# SCH_HUD_Speedo_EasyEDA.net
KiCad netlist of a schematic drawn in EasyEDA
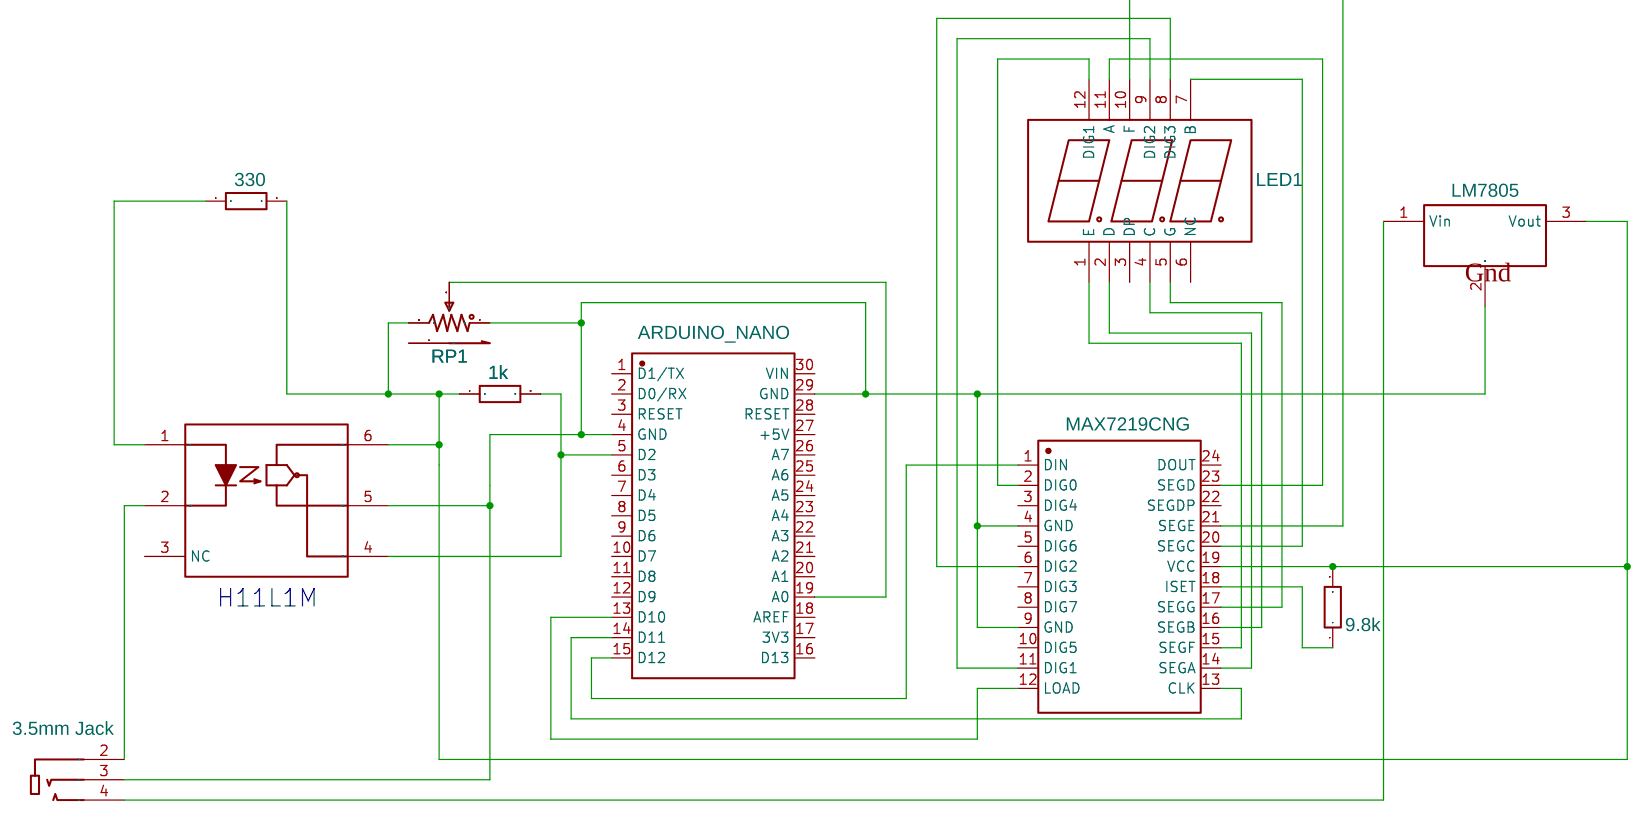
[diagram p0: schematic sheet]

(export (version "E")
  (design (tool "Eeschema 10.0.6"))
  (components
    (comp (ref "ARDUINO_NANO")
      (value "ARDUINO_NANO")
      (fields (field (name "BOM_Supplier Part") "C9900017879"))
      (libsource (lib "") (part "ARDUINO_NANO"))
    )
    (comp (ref "CN1")
      (value "3.5mm Jack")
      (fields (field (name "BOM_Manufacturer Part") "PJ-3136-B") (field (name "BOM_Supplier Part") "C381131"))
      (libsource (lib "") (part "PJ-3136-B"))
    )
    (comp (ref "DA1") (value "LM7805") (libsource (lib "") (part "LM7805")))
    (comp (ref "LED1")
      (value "SLR0523DWC1BD")
      (fields (field (name "BOM_Supplier Part") "C225931"))
      (libsource (lib "") (part "SLR0523DWC1BD"))
    )
    (comp (ref "R1")
      (value "9.8k")
      (fields
        (field (name "BOM_Manufacturer Part") "MFR0W4F1503A50")
        (field (name "BOM_Supplier Part") "C58618")
      )
      (libsource (lib "") (part "MFR0W4F1503A50_1"))
    )
    (comp (ref "R2")
      (value "330")
      (fields
        (field (name "BOM_Manufacturer Part") "MFR0W4F1503A50")
        (field (name "BOM_Supplier Part") "C58618")
      )
      (libsource (lib "") (part "MFR0W4F1503A50"))
    )
    (comp (ref "R3")
      (value "1k")
      (fields
        (field (name "BOM_Manufacturer Part") "MFR0W4F1503A50")
        (field (name "BOM_Supplier Part") "C58618")
      )
      (libsource (lib "") (part "MFR0W4F1503A50"))
    )
    (comp (ref "RP1")
      (value "RK09K1130ACM")
      (fields (field (name "BOM_Supplier Part") "C470290"))
      (libsource (lib "") (part "RK09K1130ACM"))
    )
    (comp (ref "U1")
      (value "MAX7219CNG")
      (fields (field (name "BOM_Manufacturer Part") "max7219cng") (field (name "BOM_Supplier Part") "C29160"))
      (libsource (lib "") (part "max7219cng"))
    )
    (comp (ref "U5")
      (value "H11L1M")
      (fields (field (name "BOM_Supplier Part") "C16587"))
      (libsource (lib "") (part "H11L1M"))
    )
  )
  (nets
    (net (code "1") (name "Net-(ARDUINO_NANO-A0)") (class "Default")
      (node (ref "ARDUINO_NANO") (pin "19") (pinfunction "A0_19") (pintype "unspecified"))
      (node (ref "RP1") (pin "2") (pinfunction "2_2") (pintype "unspecified"))
    )
    (net (code "2") (name "Net-(ARDUINO_NANO-D2)") (class "Default")
      (node (ref "ARDUINO_NANO") (pin "5") (pinfunction "D2_5") (pintype "unspecified"))
      (node (ref "R3") (pin "2") (pinfunction "2_2") (pintype "input"))
      (node (ref "U5") (pin "4") (pinfunction "VO_4") (pintype "unspecified"))
    )
    (net (code "3") (name "Net-(ARDUINO_NANO-D10)") (class "Default")
      (node (ref "ARDUINO_NANO") (pin "13") (pinfunction "D10_13") (pintype "unspecified"))
      (node (ref "U1") (pin "12") (pinfunction "LOAD_12") (pintype "unspecified"))
    )
    (net (code "4") (name "Net-(ARDUINO_NANO-D11)") (class "Default")
      (node (ref "ARDUINO_NANO") (pin "14") (pinfunction "D11_14") (pintype "unspecified"))
      (node (ref "U1") (pin "13") (pinfunction "CLK_13") (pintype "unspecified"))
    )
    (net (code "5") (name "Net-(ARDUINO_NANO-D12)") (class "Default")
      (node (ref "ARDUINO_NANO") (pin "15") (pinfunction "D12_15") (pintype "unspecified"))
      (node (ref "U1") (pin "1") (pinfunction "DIN_1") (pintype "unspecified"))
    )
    (net (code "6") (name "Net-(DA1-GND)") (class "Default")
      (node (ref "ARDUINO_NANO") (pin "29") (pinfunction "GND_29") (pintype "unspecified"))
      (node (ref "ARDUINO_NANO") (pin "4") (pinfunction "GND_4") (pintype "unspecified"))
      (node (ref "CN1") (pin "3") (pinfunction "3_3") (pintype "unspecified"))
      (node (ref "DA1") (pin "2") (pinfunction "GND_2") (pintype "unspecified"))
      (node (ref "RP1") (pin "1") (pinfunction "1_1") (pintype "unspecified"))
      (node (ref "U1") (pin "4") (pinfunction "GND_4") (pintype "unspecified"))
      (node (ref "U1") (pin "9") (pinfunction "GND_9") (pintype "unspecified"))
      (node (ref "U5") (pin "5") (pinfunction "GND_5") (pintype "unspecified"))
    )
    (net (code "7") (name "Net-(DA1-Vin)") (class "Default")
      (node (ref "CN1") (pin "4") (pinfunction "4_4") (pintype "unspecified"))
      (node (ref "DA1") (pin "1") (pinfunction "Vin_1") (pintype "unspecified"))
    )
    (net (code "8") (name "Net-(DA1-Vout)") (class "Default")
      (node (ref "DA1") (pin "3") (pinfunction "Vout_3") (pintype "unspecified"))
      (node (ref "R1") (pin "2") (pinfunction "2_2") (pintype "input"))
      (node (ref "R2") (pin "2") (pinfunction "2_2") (pintype "input"))
      (node (ref "R3") (pin "1") (pinfunction "1_1") (pintype "input"))
      (node (ref "RP1") (pin "3") (pinfunction "3_3") (pintype "unspecified"))
      (node (ref "U1") (pin "19") (pinfunction "VCC_19") (pintype "unspecified"))
      (node (ref "U5") (pin "6") (pinfunction "VCC_6") (pintype "unspecified"))
    )
    (net (code "9") (name "Net-(LED1-A)") (class "Default")
      (node (ref "LED1") (pin "11") (pinfunction "A_11") (pintype "unspecified"))
      (node (ref "U1") (pin "23") (pinfunction "SEGD_23") (pintype "unspecified"))
    )
    (net (code "10") (name "Net-(LED1-B)") (class "Default")
      (node (ref "LED1") (pin "7") (pinfunction "B_7") (pintype "unspecified"))
      (node (ref "U1") (pin "20") (pinfunction "SEGC_20") (pintype "unspecified"))
    )
    (net (code "11") (name "Net-(LED1-C)") (class "Default")
      (node (ref "LED1") (pin "4") (pinfunction "C_4") (pintype "unspecified"))
      (node (ref "U1") (pin "16") (pinfunction "SEGB_16") (pintype "unspecified"))
    )
    (net (code "12") (name "Net-(LED1-D)") (class "Default")
      (node (ref "LED1") (pin "2") (pinfunction "D_2") (pintype "unspecified"))
      (node (ref "U1") (pin "14") (pinfunction "SEGA_14") (pintype "unspecified"))
    )
    (net (code "13") (name "Net-(LED1-DIG1)") (class "Default")
      (node (ref "LED1") (pin "12") (pinfunction "DIG1_12") (pintype "unspecified"))
      (node (ref "U1") (pin "2") (pinfunction "DIG0_2") (pintype "unspecified"))
    )
    (net (code "14") (name "Net-(LED1-DIG2)") (class "Default")
      (node (ref "LED1") (pin "9") (pinfunction "DIG2_9") (pintype "unspecified"))
      (node (ref "U1") (pin "11") (pinfunction "DIG1_11") (pintype "unspecified"))
    )
    (net (code "15") (name "Net-(LED1-DIG3)") (class "Default")
      (node (ref "LED1") (pin "8") (pinfunction "DIG3_8") (pintype "unspecified"))
      (node (ref "U1") (pin "6") (pinfunction "DIG2_6") (pintype "unspecified"))
    )
    (net (code "16") (name "Net-(LED1-E)") (class "Default")
      (node (ref "LED1") (pin "1") (pinfunction "E_1") (pintype "unspecified"))
      (node (ref "U1") (pin "15") (pinfunction "SEGF_15") (pintype "unspecified"))
    )
    (net (code "17") (name "Net-(LED1-F)") (class "Default")
      (node (ref "LED1") (pin "10") (pinfunction "F_10") (pintype "unspecified"))
      (node (ref "U1") (pin "21") (pinfunction "SEGE_21") (pintype "unspecified"))
    )
    (net (code "18") (name "Net-(LED1-G)") (class "Default")
      (node (ref "LED1") (pin "5") (pinfunction "G_5") (pintype "unspecified"))
      (node (ref "U1") (pin "17") (pinfunction "SEGG_17") (pintype "unspecified"))
    )
    (net (code "19") (name "Net-(U1-ISET)") (class "Default")
      (node (ref "R1") (pin "1") (pinfunction "1_1") (pintype "input"))
      (node (ref "U1") (pin "18") (pinfunction "ISET_18") (pintype "unspecified"))
    )
    (net (code "20") (name "Net-(U5-AN)") (class "Default")
      (node (ref "R2") (pin "1") (pinfunction "1_1") (pintype "input"))
      (node (ref "U5") (pin "1") (pinfunction "AN_1") (pintype "unspecified"))
    )
    (net (code "21") (name "Net-(U5-CAT)") (class "Default")
      (node (ref "CN1") (pin "2") (pinfunction "2_2") (pintype "unspecified"))
      (node (ref "U5") (pin "2") (pinfunction "CAT_2") (pintype "unspecified"))
    )
    (net (code "22") (name "unconnected-(ARDUINO_NANO-+5V-Pad27)") (class "Default")
      (node (ref "ARDUINO_NANO") (pin "27") (pinfunction "+5V_27") (pintype "unspecified"))
    )
    (net (code "23") (name "unconnected-(ARDUINO_NANO-3V3-Pad17)") (class "Default")
      (node (ref "ARDUINO_NANO") (pin "17") (pinfunction "3V3_17") (pintype "unspecified"))
    )
    (net (code "24") (name "unconnected-(ARDUINO_NANO-A1-Pad20)") (class "Default")
      (node (ref "ARDUINO_NANO") (pin "20") (pinfunction "A1_20") (pintype "unspecified"))
    )
    (net (code "25") (name "unconnected-(ARDUINO_NANO-A2-Pad21)") (class "Default")
      (node (ref "ARDUINO_NANO") (pin "21") (pinfunction "A2_21") (pintype "unspecified"))
    )
    (net (code "26") (name "unconnected-(ARDUINO_NANO-A3-Pad22)") (class "Default")
      (node (ref "ARDUINO_NANO") (pin "22") (pinfunction "A3_22") (pintype "unspecified"))
    )
    (net (code "27") (name "unconnected-(ARDUINO_NANO-A4-Pad23)") (class "Default")
      (node (ref "ARDUINO_NANO") (pin "23") (pinfunction "A4_23") (pintype "unspecified"))
    )
    (net (code "28") (name "unconnected-(ARDUINO_NANO-A5-Pad24)") (class "Default")
      (node (ref "ARDUINO_NANO") (pin "24") (pinfunction "A5_24") (pintype "unspecified"))
    )
    (net (code "29") (name "unconnected-(ARDUINO_NANO-A6-Pad25)") (class "Default")
      (node (ref "ARDUINO_NANO") (pin "25") (pinfunction "A6_25") (pintype "unspecified"))
    )
    (net (code "30") (name "unconnected-(ARDUINO_NANO-A7-Pad26)") (class "Default")
      (node (ref "ARDUINO_NANO") (pin "26") (pinfunction "A7_26") (pintype "unspecified"))
    )
    (net (code "31") (name "unconnected-(ARDUINO_NANO-AREF-Pad18)") (class "Default")
      (node (ref "ARDUINO_NANO") (pin "18") (pinfunction "AREF_18") (pintype "unspecified"))
    )
    (net (code "32") (name "unconnected-(ARDUINO_NANO-D0{slash}RX-Pad2)") (class "Default")
      (node (ref "ARDUINO_NANO") (pin "2") (pinfunction "D0/RX_2") (pintype "unspecified"))
    )
    (net (code "33") (name "unconnected-(ARDUINO_NANO-D1{slash}TX-Pad1)") (class "Default")
      (node (ref "ARDUINO_NANO") (pin "1") (pinfunction "D1/TX_1") (pintype "unspecified"))
    )
    (net (code "34") (name "unconnected-(ARDUINO_NANO-D3-Pad6)") (class "Default")
      (node (ref "ARDUINO_NANO") (pin "6") (pinfunction "D3_6") (pintype "unspecified"))
    )
    (net (code "35") (name "unconnected-(ARDUINO_NANO-D4-Pad7)") (class "Default")
      (node (ref "ARDUINO_NANO") (pin "7") (pinfunction "D4_7") (pintype "unspecified"))
    )
    (net (code "36") (name "unconnected-(ARDUINO_NANO-D5-Pad8)") (class "Default")
      (node (ref "ARDUINO_NANO") (pin "8") (pinfunction "D5_8") (pintype "unspecified"))
    )
    (net (code "37") (name "unconnected-(ARDUINO_NANO-D6-Pad9)") (class "Default")
      (node (ref "ARDUINO_NANO") (pin "9") (pinfunction "D6_9") (pintype "unspecified"))
    )
    (net (code "38") (name "unconnected-(ARDUINO_NANO-D7-Pad10)") (class "Default")
      (node (ref "ARDUINO_NANO") (pin "10") (pinfunction "D7_10") (pintype "unspecified"))
    )
    (net (code "39") (name "unconnected-(ARDUINO_NANO-D8-Pad11)") (class "Default")
      (node (ref "ARDUINO_NANO") (pin "11") (pinfunction "D8_11") (pintype "unspecified"))
    )
    (net (code "40") (name "unconnected-(ARDUINO_NANO-D9-Pad12)") (class "Default")
      (node (ref "ARDUINO_NANO") (pin "12") (pinfunction "D9_12") (pintype "unspecified"))
    )
    (net (code "41") (name "unconnected-(ARDUINO_NANO-D13-Pad16)") (class "Default")
      (node (ref "ARDUINO_NANO") (pin "16") (pinfunction "D13_16") (pintype "unspecified"))
    )
    (net (code "42") (name "unconnected-(ARDUINO_NANO-RESET-Pad3)") (class "Default")
      (node (ref "ARDUINO_NANO") (pin "3") (pinfunction "RESET_3") (pintype "unspecified"))
    )
    (net (code "43") (name "unconnected-(ARDUINO_NANO-RESET-Pad28)") (class "Default")
      (node (ref "ARDUINO_NANO") (pin "28") (pinfunction "RESET_28") (pintype "unspecified"))
    )
    (net (code "44") (name "unconnected-(ARDUINO_NANO-VIN-Pad30)") (class "Default")
      (node (ref "ARDUINO_NANO") (pin "30") (pinfunction "VIN_30") (pintype "unspecified"))
    )
    (net (code "45") (name "unconnected-(LED1-DP-Pad3)") (class "Default")
      (node (ref "LED1") (pin "3") (pinfunction "DP_3") (pintype "unspecified"))
    )
    (net (code "46") (name "unconnected-(LED1-NC-Pad6)") (class "Default")
      (node (ref "LED1") (pin "6") (pinfunction "NC_6") (pintype "unspecified"))
    )
    (net (code "47") (name "unconnected-(RP1-Pad4)") (class "Default")
      (node (ref "RP1") (pin "4") (pinfunction "4_4") (pintype "unspecified"))
    )
    (net (code "48") (name "unconnected-(U1-DIG3-Pad7)") (class "Default")
      (node (ref "U1") (pin "7") (pinfunction "DIG3_7") (pintype "unspecified"))
    )
    (net (code "49") (name "unconnected-(U1-DIG4-Pad3)") (class "Default")
      (node (ref "U1") (pin "3") (pinfunction "DIG4_3") (pintype "unspecified"))
    )
    (net (code "50") (name "unconnected-(U1-DIG5-Pad10)") (class "Default")
      (node (ref "U1") (pin "10") (pinfunction "DIG5_10") (pintype "unspecified"))
    )
    (net (code "51") (name "unconnected-(U1-DIG6-Pad5)") (class "Default")
      (node (ref "U1") (pin "5") (pinfunction "DIG6_5") (pintype "unspecified"))
    )
    (net (code "52") (name "unconnected-(U1-DIG7-Pad8)") (class "Default")
      (node (ref "U1") (pin "8") (pinfunction "DIG7_8") (pintype "unspecified"))
    )
    (net (code "53") (name "unconnected-(U1-DOUT-Pad24)") (class "Default")
      (node (ref "U1") (pin "24") (pinfunction "DOUT_24") (pintype "unspecified"))
    )
    (net (code "54") (name "unconnected-(U1-SEGDP-Pad22)") (class "Default")
      (node (ref "U1") (pin "22") (pinfunction "SEGDP_22") (pintype "unspecified"))
    )
    (net (code "55") (name "unconnected-(U5-NC-Pad3)") (class "Default")
      (node (ref "U5") (pin "3") (pinfunction "NC_3") (pintype "unspecified"))
    )
  )
)
